# PowerSupp.net
KiCad netlist of a schematic drawn in Altium Designer
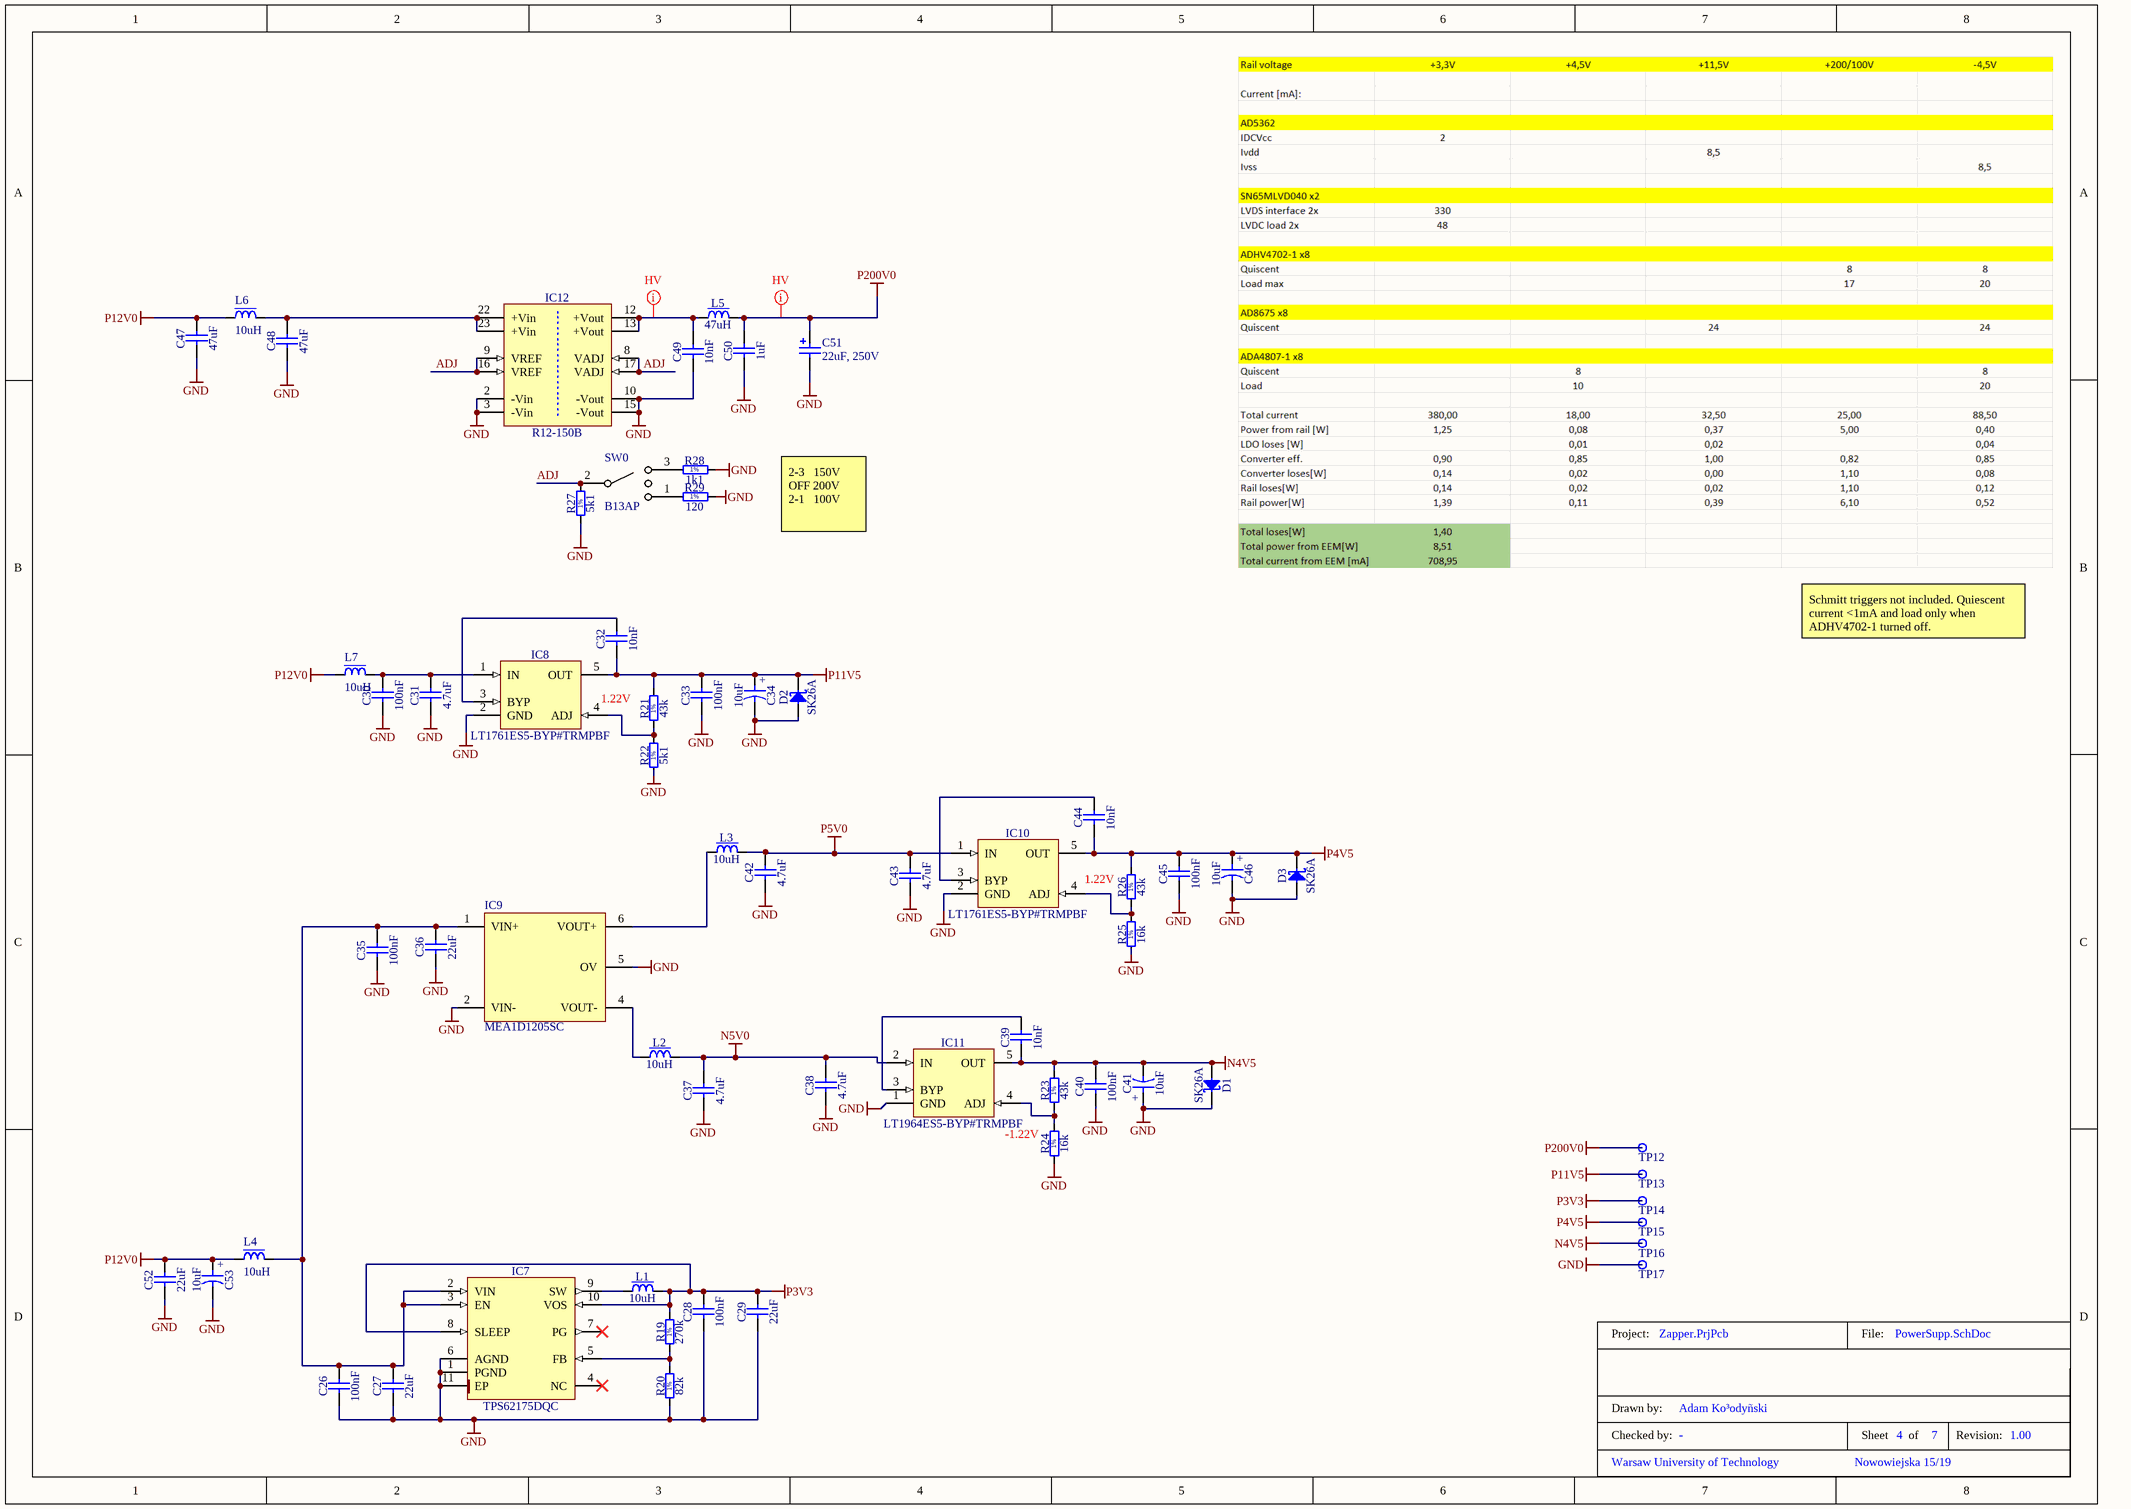
[diagram p0: PowerSupp.SchDoc]

(export (version "E")
  (design (tool "Eeschema 10.0.6"))
  (components
    (comp (ref "C26")
      (value "100nF")
      (footprint "CAPC1005X55N")
      (description "Non-polarised capacitor")
      (fields
        (field (name "PART NUMBER") "CC0402_100NF_16V_10%_X7R")
        (field (name "VOLTAGE") "16V")
        (field (name "AUTHOR") "CERN DEM JLC")
      )
      (libsource (lib "Capacitors") (part "Capacitor - non polarized"))
    )
    (comp (ref "C27")
      (value "22uF")
      (footprint "CAPC2012X135N")
      (description "Non-polarised capacitor")
      (fields
        (field (name "PART NUMBER") "CC0805_22UF_16V_10%_X5R")
        (field (name "VOLTAGE") "16V")
        (field (name "AUTHOR") "CERN DEM JLC")
      )
      (libsource (lib "Capacitors") (part "Capacitor - non polarized"))
    )
    (comp (ref "C28")
      (value "100nF")
      (footprint "CAPC1005X55N")
      (description "Non-polarised capacitor")
      (fields
        (field (name "PART NUMBER") "CC0402_100NF_16V_10%_X7R")
        (field (name "VOLTAGE") "16V")
        (field (name "AUTHOR") "CERN DEM JLC")
      )
      (libsource (lib "Capacitors") (part "Capacitor - non polarized"))
    )
    (comp (ref "C29")
      (value "22uF")
      (footprint "CAPC2012X135N")
      (description "Non-polarised capacitor")
      (fields
        (field (name "PART NUMBER") "CC0805_22UF_16V_10%_X5R")
        (field (name "VOLTAGE") "16V")
        (field (name "AUTHOR") "CERN DEM JLC")
      )
      (libsource (lib "Capacitors") (part "Capacitor - non polarized"))
    )
    (comp (ref "C30")
      (value "100nF")
      (footprint "CAPC1005X55N")
      (description "Non-polarised capacitor")
      (fields
        (field (name "PART NUMBER") "CC0402_100NF_16V_10%_X7R")
        (field (name "VOLTAGE") "16V")
        (field (name "AUTHOR") "CERN DEM JLC")
      )
      (libsource (lib "Capacitors") (part "Capacitor - non polarized"))
    )
    (comp (ref "C31")
      (value "4.7uF")
      (footprint "CAPC2012X135N")
      (description "Non-polarised capacitor")
      (fields
        (field (name "PART NUMBER") "CC0805_4.7UF_16V_10%_X7R")
        (field (name "VOLTAGE") "16V")
        (field (name "AUTHOR") "CERN DEM JLC")
      )
      (libsource (lib "Capacitors") (part "Capacitor - non polarized"))
    )
    (comp (ref "C32")
      (value "10nF")
      (footprint "CAPC1608X87N")
      (description "Non-polarised capacitor")
      (fields
        (field (name "PART NUMBER") "CC0603_10NF_50V_10%_X7R")
        (field (name "VOLTAGE") "50V")
        (field (name "AUTHOR") "CERN DEM JLC")
      )
      (libsource (lib "Capacitors") (part "Capacitor - non polarized"))
    )
    (comp (ref "C33")
      (value "100nF")
      (footprint "CAPC1005X55N")
      (description "Non-polarised capacitor")
      (fields
        (field (name "PART NUMBER") "CC0402_100NF_16V_10%_X7R")
        (field (name "VOLTAGE") "16V")
        (field (name "AUTHOR") "CERN DEM JLC")
      )
      (libsource (lib "Capacitors") (part "Capacitor - non polarized"))
    )
    (comp (ref "C34")
      (value "10uF")
      (footprint "CAPMP3528X210N")
      (description "Polarised capacitor")
      (fields
        (field (name "PART NUMBER") "CTE3528-21_10UF_16V_20%_PANASONIC_TQC")
        (field (name "VOLTAGE") "16V")
        (field (name "AUTHOR") "CERN DEM JLC")
      )
      (libsource (lib "Capacitors") (part "Capacitor - polarized"))
    )
    (comp (ref "C35")
      (value "100nF")
      (footprint "CAPC1005X55N")
      (description "Non-polarised capacitor")
      (fields
        (field (name "PART NUMBER") "CC0402_100NF_16V_10%_X7R")
        (field (name "VOLTAGE") "16V")
        (field (name "AUTHOR") "CERN DEM JLC")
      )
      (libsource (lib "Capacitors") (part "Capacitor - non polarized"))
    )
    (comp (ref "C36")
      (value "22uF")
      (footprint "CAPC2012X135N")
      (description "Non-polarised capacitor")
      (fields
        (field (name "PART NUMBER") "CC0805_22UF_16V_10%_X5R")
        (field (name "VOLTAGE") "16V")
        (field (name "AUTHOR") "CERN DEM JLC")
      )
      (libsource (lib "Capacitors") (part "Capacitor - non polarized"))
    )
    (comp (ref "C37")
      (value "4.7uF")
      (footprint "CAPC2012X135N")
      (description "Non-polarised capacitor")
      (fields
        (field (name "PART NUMBER") "CC0805_4.7UF_16V_10%_X7R")
        (field (name "VOLTAGE") "16V")
        (field (name "AUTHOR") "CERN DEM JLC")
      )
      (libsource (lib "Capacitors") (part "Capacitor - non polarized"))
    )
    (comp (ref "C38")
      (value "4.7uF")
      (footprint "CAPC2012X135N")
      (description "Non-polarised capacitor")
      (fields
        (field (name "PART NUMBER") "CC0805_4.7UF_16V_10%_X7R")
        (field (name "VOLTAGE") "16V")
        (field (name "AUTHOR") "CERN DEM JLC")
      )
      (libsource (lib "Capacitors") (part "Capacitor - non polarized"))
    )
    (comp (ref "C39")
      (value "10nF")
      (footprint "CAPC1608X87N")
      (description "Non-polarised capacitor")
      (fields
        (field (name "PART NUMBER") "CC0603_10NF_50V_10%_X7R")
        (field (name "VOLTAGE") "50V")
        (field (name "AUTHOR") "CERN DEM JLC")
      )
      (libsource (lib "Capacitors") (part "Capacitor - non polarized"))
    )
    (comp (ref "C40")
      (value "100nF")
      (footprint "CAPC1005X55N")
      (description "Non-polarised capacitor")
      (fields
        (field (name "PART NUMBER") "CC0402_100NF_16V_10%_X7R")
        (field (name "VOLTAGE") "16V")
        (field (name "AUTHOR") "CERN DEM JLC")
      )
      (libsource (lib "Capacitors") (part "Capacitor - non polarized"))
    )
    (comp (ref "C41")
      (value "10uF")
      (footprint "CAPMP3528X210N")
      (description "Polarised capacitor")
      (fields
        (field (name "PART NUMBER") "CTE3528-21_10UF_16V_20%_PANASONIC_TQC")
        (field (name "VOLTAGE") "16V")
        (field (name "AUTHOR") "CERN DEM JLC")
      )
      (libsource (lib "Capacitors") (part "Capacitor - polarized"))
    )
    (comp (ref "C42")
      (value "4.7uF")
      (footprint "CAPC2012X135N")
      (description "Non-polarised capacitor")
      (fields
        (field (name "PART NUMBER") "CC0805_4.7UF_16V_10%_X7R")
        (field (name "VOLTAGE") "16V")
        (field (name "AUTHOR") "CERN DEM JLC")
      )
      (libsource (lib "Capacitors") (part "Capacitor - non polarized"))
    )
    (comp (ref "C43")
      (value "4.7uF")
      (footprint "CAPC2012X135N")
      (description "Non-polarised capacitor")
      (fields
        (field (name "PART NUMBER") "CC0805_4.7UF_16V_10%_X7R")
        (field (name "VOLTAGE") "16V")
        (field (name "AUTHOR") "CERN DEM JLC")
      )
      (libsource (lib "Capacitors") (part "Capacitor - non polarized"))
    )
    (comp (ref "C44")
      (value "10nF")
      (footprint "CAPC1608X87N")
      (description "Non-polarised capacitor")
      (fields
        (field (name "PART NUMBER") "CC0603_10NF_50V_10%_X7R")
        (field (name "VOLTAGE") "50V")
        (field (name "AUTHOR") "CERN DEM JLC")
      )
      (libsource (lib "Capacitors") (part "Capacitor - non polarized"))
    )
    (comp (ref "C45")
      (value "100nF")
      (footprint "CAPC1005X55N")
      (description "Non-polarised capacitor")
      (fields
        (field (name "PART NUMBER") "CC0402_100NF_16V_10%_X7R")
        (field (name "VOLTAGE") "16V")
        (field (name "AUTHOR") "CERN DEM JLC")
      )
      (libsource (lib "Capacitors") (part "Capacitor - non polarized"))
    )
    (comp (ref "C46")
      (value "10uF")
      (footprint "CAPMP3528X210N")
      (description "Polarised capacitor")
      (fields
        (field (name "PART NUMBER") "CTE3528-21_10UF_16V_20%_PANASONIC_TQC")
        (field (name "VOLTAGE") "16V")
        (field (name "AUTHOR") "CERN DEM JLC")
      )
      (libsource (lib "Capacitors") (part "Capacitor - polarized"))
    )
    (comp (ref "C47")
      (value "47uF")
      (footprint "CAPC5750X200N")
      (description "Non-polarised capacitor")
      (fields
        (field (name "PART NUMBER") "CC2220_47UF_16V_20%_X7R")
        (field (name "VOLTAGE") "16V")
        (field (name "AUTHOR") "CERN DEM JLC")
      )
      (libsource (lib "Capacitors") (part "Capacitor - non polarized"))
    )
    (comp (ref "C48")
      (value "47uF")
      (footprint "CAPC5750X200N")
      (description "Non-polarised capacitor")
      (fields
        (field (name "PART NUMBER") "CC2220_47UF_16V_20%_X7R")
        (field (name "VOLTAGE") "16V")
        (field (name "AUTHOR") "CERN DEM JLC")
      )
      (libsource (lib "Capacitors") (part "Capacitor - non polarized"))
    )
    (comp (ref "C49")
      (value "10nF")
      (footprint "CAPC3216X88N")
      (description "Non-polarised capacitor")
      (fields
        (field (name "PART NUMBER") "CC1206_10NF_250V_10%_X7R")
        (field (name "VOLTAGE") "250V")
        (field (name "AUTHOR") "CERN DEM MR")
      )
      (libsource (lib "Capacitors") (part "Capacitor - non polarized"))
    )
    (comp (ref "C50")
      (value "1uF")
      (footprint "CAPC5750X270N")
      (description "Non-polarised capacitor")
      (fields
        (field (name "PART NUMBER") "CC2220_1UF_250V_10%_X7T_MURATA_GC355XD72E105KX05L")
        (field (name "VOLTAGE") "250V")
        (field (name "AUTHOR") "CERN DEM JLC")
      )
      (libsource (lib "Capacitors") (part "Capacitor - non polarized"))
    )
    (comp (ref "C51")
      (value "22uF, 250V")
      (footprint "WCAP-AT1H_13x20")
      (description "WCAP-AT1H Aluminum Electrolytic Capacitor, Radial, THT, D13xH20mm, 22uF, 250V")
      (fields
        (field (name "MANUFACTURER PART NUMBER") "860241178002")
        (field (name "MANUFACTURER") "Wurth Elektronik")
      )
      (libsource (lib "CapacitorLibrary") (part "860241178002"))
    )
    (comp (ref "C52")
      (value "22uF")
      (footprint "CAPC2012X135N")
      (description "Non-polarised capacitor")
      (fields
        (field (name "PART NUMBER") "CC0805_22UF_16V_10%_X5R")
        (field (name "VOLTAGE") "16V")
        (field (name "AUTHOR") "CERN DEM JLC")
      )
      (libsource (lib "Capacitors") (part "Capacitor - non polarized"))
    )
    (comp (ref "C53")
      (value "10uF")
      (footprint "CAPMP3528X210N")
      (description "Polarised capacitor")
      (fields
        (field (name "PART NUMBER") "CTE3528-21_10UF_16V_20%_PANASONIC_TQC")
        (field (name "VOLTAGE") "16V")
        (field (name "AUTHOR") "CERN DEM JLC")
      )
      (libsource (lib "Capacitors") (part "Capacitor - polarized"))
    )
    (comp (ref "D1")
      (value "SK26A")
      (footprint "DIOM5126X265N")
      (description "Schottky Diode")
      (fields
        (field (name "VOLTAGE") "60V")
        (field (name "POWER") "2A")
        (field (name "AUTHOR") "CERN DEM JMW")
      )
      (libsource (lib "ICs And Semiconductors") (part "Diode Schottky"))
    )
    (comp (ref "D2")
      (value "SK26A")
      (footprint "DIOM5126X265N")
      (description "Schottky Diode")
      (fields
        (field (name "VOLTAGE") "60V")
        (field (name "POWER") "2A")
        (field (name "AUTHOR") "CERN DEM JMW")
      )
      (libsource (lib "ICs And Semiconductors") (part "Diode Schottky"))
    )
    (comp (ref "D3")
      (value "SK26A")
      (footprint "DIOM5126X265N")
      (description "Schottky Diode")
      (fields
        (field (name "VOLTAGE") "60V")
        (field (name "POWER") "2A")
        (field (name "AUTHOR") "CERN DEM JMW")
      )
      (libsource (lib "ICs And Semiconductors") (part "Diode Schottky"))
    )
    (comp (ref "IC7")
      (value "TPS62175DQC")
      (footprint "SON50P200X300X80-11N-R94X250")
      (description "4.75-28VDC to 1-6VDC, 500mA Step-Down Converter With Sleep Mode")
      (fields (field (name "MANUFACTURER") "TEXAS INSTRUMENTS") (field (name "AUTHOR") "CERN DEM JMW"))
      (libsource (lib "ICs And Semiconductors") (part "TPS62175"))
    )
    (comp (ref "IC8")
      (value "LT1761ES5-BYP#TRMPBF")
      (footprint "SOT95P280X100-5N")
      (description "100mA, Low Noise, LDO Micropower Adjustable Regulator in SOT-23")
      (fields (field (name "MANUFACTURER") "LINEAR TECHNOLOGY") (field (name "AUTHOR") "CERN DEM MR"))
      (libsource (lib "ICs And Semiconductors") (part "LT1761-BYP"))
    )
    (comp (ref "IC9")
      (value "MEA1D1205SC")
      (footprint "MURA-SIP-5_V")
      (description "Module DC-DC 2-OUT 5V/-5V 0.1A/-0.1A 1W 5-Pin SIP Tube")
      (libsource (lib "InzLib") (part "MEA1D1205SC"))
    )
    (comp (ref "IC10")
      (value "LT1761ES5-BYP#TRMPBF")
      (footprint "SOT95P280X100-5N")
      (description "100mA, Low Noise, LDO Micropower Adjustable Regulator in SOT-23")
      (fields (field (name "MANUFACTURER") "LINEAR TECHNOLOGY") (field (name "AUTHOR") "CERN DEM MR"))
      (libsource (lib "ICs And Semiconductors") (part "LT1761-BYP"))
    )
    (comp (ref "IC11")
      (value "LT1964ES5-BYP#TRMPBF")
      (footprint "SOT95P280X100-5N")
      (description "200mA, Low Noise, Low Dropout Negative Micropower Regulator")
      (fields (field (name "MANUFACTURER") "LINEAR TECHNOLOGY") (field (name "AUTHOR") "CERN DEM MR"))
      (libsource (lib "ICs And Semiconductors") (part "LT1964-BYP"))
    )
    (comp (ref "IC12")
      (value "R12-150B")
      (footprint "DCDC_RECOM_Rxx-B")
      (description "RECOM, Rxx-B Series, Single Output DCDC Converter")
      (fields (field (name "MANUFACTURER") "RECOM") (field (name "AUTHOR") "CERN DEM MR"))
      (libsource (lib "ICs And Semiconductors") (part "DCDC_RECOM_Rxx-B_Single Output"))
    )
    (comp (ref "L1")
      (value "10uH")
      (footprint "IND_MURATA-PS_8400")
      (description "Inductor With Core")
      (fields
        (field (name "PART NUMBER") "IND_10UH_10%_MURATA-PS_8400")
        (field (name "POWER") "950mA")
        (field (name "AUTHOR") "CERN DEM JLC")
      )
      (libsource (lib "Inductors & Transformers") (part "Inductor With Magnetic core"))
    )
    (comp (ref "L2")
      (value "10uH")
      (footprint "IND_MURATA-PS_8400")
      (description "Inductor With Core")
      (fields
        (field (name "PART NUMBER") "IND_10UH_10%_MURATA-PS_8400")
        (field (name "POWER") "950mA")
        (field (name "AUTHOR") "CERN DEM JLC")
      )
      (libsource (lib "Inductors & Transformers") (part "Inductor With Magnetic core"))
    )
    (comp (ref "L3")
      (value "10uH")
      (footprint "IND_MURATA-PS_8400")
      (description "Inductor With Core")
      (fields
        (field (name "PART NUMBER") "IND_10UH_10%_MURATA-PS_8400")
        (field (name "POWER") "950mA")
        (field (name "AUTHOR") "CERN DEM JLC")
      )
      (libsource (lib "Inductors & Transformers") (part "Inductor With Magnetic core"))
    )
    (comp (ref "L4")
      (value "10uH")
      (footprint "IND_MURATA-PS_8400")
      (description "Inductor With Core")
      (fields
        (field (name "PART NUMBER") "IND_10UH_10%_MURATA-PS_8400")
        (field (name "POWER") "950mA")
        (field (name "AUTHOR") "CERN DEM JLC")
      )
      (libsource (lib "Inductors & Transformers") (part "Inductor With Magnetic core"))
    )
    (comp (ref "L5")
      (value "47uH")
      (footprint "IND_MURATA-PS_8400")
      (description "Inductor With Core")
      (fields
        (field (name "PART NUMBER") "IND_47UH_10%_MURATA-PS_8400")
        (field (name "POWER") "420mA")
        (field (name "AUTHOR") "CERN DEM JLC")
      )
      (libsource (lib "Inductors & Transformers") (part "Inductor With Magnetic core"))
    )
    (comp (ref "L6")
      (value "10uH")
      (footprint "IND_MURATA-PS_8400")
      (description "Inductor With Core")
      (fields
        (field (name "PART NUMBER") "IND_10UH_10%_MURATA-PS_8400")
        (field (name "POWER") "950mA")
        (field (name "AUTHOR") "CERN DEM JLC")
      )
      (libsource (lib "Inductors & Transformers") (part "Inductor With Magnetic core"))
    )
    (comp (ref "L7")
      (value "10uH")
      (footprint "IND_MURATA-PS_8400")
      (description "Inductor With Core")
      (fields
        (field (name "PART NUMBER") "IND_10UH_10%_MURATA-PS_8400")
        (field (name "POWER") "950mA")
        (field (name "AUTHOR") "CERN DEM JLC")
      )
      (libsource (lib "Inductors & Transformers") (part "Inductor With Magnetic core"))
    )
    (comp (ref "R19")
      (value "270k")
      (footprint "RESC1608X55N")
      (description "Resistor - 1%")
      (fields
        (field (name "PART NUMBER") "R0603_270K_1%_0.1W_100PPM")
        (field (name "POWER") "0.1W")
        (field (name "AUTHOR") "CERN DEM JLC")
      )
      (libsource (lib "Resistors") (part "Resistor - 1%"))
    )
    (comp (ref "R20")
      (value "82k")
      (footprint "RESC1608X55N")
      (description "Resistor - 1%")
      (fields
        (field (name "PART NUMBER") "R0603_82K_1%_0.1W_100PPM")
        (field (name "POWER") "0.1W")
        (field (name "AUTHOR") "CERN DEM JLC")
      )
      (libsource (lib "Resistors") (part "Resistor - 1%"))
    )
    (comp (ref "R21")
      (value "43k")
      (footprint "RESC1608X55N")
      (description "Resistor - 1%")
      (fields
        (field (name "PART NUMBER") "R0603_43K_1%_0.1W_100PPM")
        (field (name "POWER") "0.1W")
        (field (name "AUTHOR") "CERN DEM JLC")
      )
      (libsource (lib "Resistors") (part "Resistor - 1%"))
    )
    (comp (ref "R22")
      (value "5k1")
      (footprint "RESC1608X55N")
      (description "Resistor - 1%")
      (fields
        (field (name "PART NUMBER") "R0603_5K1_1%_0.1W_100PPM")
        (field (name "POWER") "0.1W")
        (field (name "AUTHOR") "CERN DEM JLC")
      )
      (libsource (lib "Resistors") (part "Resistor - 1%"))
    )
    (comp (ref "R23")
      (value "43k")
      (footprint "RESC1608X55N")
      (description "Resistor - 1%")
      (fields
        (field (name "PART NUMBER") "R0603_43K_1%_0.1W_100PPM")
        (field (name "POWER") "0.1W")
        (field (name "AUTHOR") "CERN DEM JLC")
      )
      (libsource (lib "Resistors") (part "Resistor - 1%"))
    )
    (comp (ref "R24")
      (value "16k")
      (footprint "RESC1608X55N")
      (description "Resistor - 1%")
      (fields
        (field (name "PART NUMBER") "R0603_16K_1%_0.1W_100PPM")
        (field (name "POWER") "0.1W")
        (field (name "AUTHOR") "CERN DEM JLC")
      )
      (libsource (lib "Resistors") (part "Resistor - 1%"))
    )
    (comp (ref "R25")
      (value "16k")
      (footprint "RESC1608X55N")
      (description "Resistor - 1%")
      (fields
        (field (name "PART NUMBER") "R0603_16K_1%_0.1W_100PPM")
        (field (name "POWER") "0.1W")
        (field (name "AUTHOR") "CERN DEM JLC")
      )
      (libsource (lib "Resistors") (part "Resistor - 1%"))
    )
    (comp (ref "R26")
      (value "43k")
      (footprint "RESC1608X55N")
      (description "Resistor - 1%")
      (fields
        (field (name "PART NUMBER") "R0603_43K_1%_0.1W_100PPM")
        (field (name "POWER") "0.1W")
        (field (name "AUTHOR") "CERN DEM JLC")
      )
      (libsource (lib "Resistors") (part "Resistor - 1%"))
    )
    (comp (ref "R27")
      (value "5k1")
      (footprint "RESC1608X55N")
      (description "Resistor - 1%")
      (fields
        (field (name "PART NUMBER") "R0603_5K1_1%_0.1W_100PPM")
        (field (name "POWER") "0.1W")
        (field (name "AUTHOR") "CERN DEM JLC")
      )
      (libsource (lib "Resistors") (part "Resistor - 1%"))
    )
    (comp (ref "R28")
      (value "1k1")
      (footprint "RESC1608X55N")
      (description "Resistor - 1%")
      (fields
        (field (name "PART NUMBER") "R0603_1K1_1%_0.1W_100PPM")
        (field (name "POWER") "0.1W")
        (field (name "AUTHOR") "CERN DEM JLC")
      )
      (libsource (lib "Resistors") (part "Resistor - 1%"))
    )
    (comp (ref "R29")
      (value "120")
      (footprint "RESC1608X55N")
      (description "Resistor - 1%")
      (fields
        (field (name "PART NUMBER") "R0603_120R_1%_0.1W_100PPM")
        (field (name "POWER") "0.1W")
        (field (name "AUTHOR") "CERN DEM JLC")
      )
      (libsource (lib "Resistors") (part "Resistor - 1%"))
    )
    (comp (ref "SW0")
      (value "B13AP")
      (footprint "B13AP")
      (description "Switch;  Sealed;  Anti-Static Toggle;  SPDT;  ON-OFF-ON;  Str PC;  No Cap;  0.4A;  28VAC/DC")
      (libsource (lib "InzLib") (part "B13AP"))
    )
    (comp (ref "TitleBlock4") (value "TitleBlock") (libsource (lib "InzLib") (part "TitleBlock")))
    (comp (ref "TP12")
      (value "Test Point")
      (footprint "TPS127")
      (fields (field (name "PART NUMBER") "SMD_PAD_1.27X1.27MM") (field (name "AUTHOR") "CERN DEM JLC"))
      (libsource (lib "Eletro-mechanical") (part "Test Point"))
    )
    (comp (ref "TP13")
      (value "Test Point")
      (footprint "TPS127")
      (fields (field (name "PART NUMBER") "SMD_PAD_1.27X1.27MM") (field (name "AUTHOR") "CERN DEM JLC"))
      (libsource (lib "Eletro-mechanical") (part "Test Point"))
    )
    (comp (ref "TP14")
      (value "Test Point")
      (footprint "TPS127")
      (fields (field (name "PART NUMBER") "SMD_PAD_1.27X1.27MM") (field (name "AUTHOR") "CERN DEM JLC"))
      (libsource (lib "Eletro-mechanical") (part "Test Point"))
    )
    (comp (ref "TP15")
      (value "Test Point")
      (footprint "TPS127")
      (fields (field (name "PART NUMBER") "SMD_PAD_1.27X1.27MM") (field (name "AUTHOR") "CERN DEM JLC"))
      (libsource (lib "Eletro-mechanical") (part "Test Point"))
    )
    (comp (ref "TP16")
      (value "Test Point")
      (footprint "TPS127")
      (fields (field (name "PART NUMBER") "SMD_PAD_1.27X1.27MM") (field (name "AUTHOR") "CERN DEM JLC"))
      (libsource (lib "Eletro-mechanical") (part "Test Point"))
    )
    (comp (ref "TP17")
      (value "Test Point")
      (footprint "TPS127")
      (fields (field (name "PART NUMBER") "SMD_PAD_1.27X1.27MM") (field (name "AUTHOR") "CERN DEM JLC"))
      (libsource (lib "Eletro-mechanical") (part "Test Point"))
    )
  )
  (nets
    (net (code "1") (name "/ADJ") (class "Default")
      (node (ref "IC12") (pin "16") (pinfunction "VREF_16") (pintype "input"))
      (node (ref "IC12") (pin "17") (pinfunction "VADJ_17") (pintype "input"))
      (node (ref "IC12") (pin "8") (pinfunction "VADJ_8") (pintype "input"))
      (node (ref "IC12") (pin "9") (pinfunction "VREF_9") (pintype "input"))
      (node (ref "R27") (pin "2") (pinfunction "2_2") (pintype "passive"))
      (node (ref "SW0") (pin "2") (pinfunction "C_2") (pintype "passive"))
    )
    (net (code "2") (name "GND") (class "Default")
      (node (ref "C26") (pin "1") (pinfunction "1_1") (pintype "passive"))
      (node (ref "C27") (pin "1") (pinfunction "1_1") (pintype "passive"))
      (node (ref "C28") (pin "1") (pinfunction "1_1") (pintype "passive"))
      (node (ref "C29") (pin "1") (pinfunction "1_1") (pintype "passive"))
      (node (ref "C30") (pin "1") (pinfunction "1_1") (pintype "passive"))
      (node (ref "C31") (pin "1") (pinfunction "1_1") (pintype "passive"))
      (node (ref "C33") (pin "1") (pinfunction "1_1") (pintype "passive"))
      (node (ref "C34") (pin "2") (pinfunction "2_2") (pintype "passive"))
      (node (ref "C35") (pin "1") (pinfunction "1_1") (pintype "passive"))
      (node (ref "C36") (pin "1") (pinfunction "1_1") (pintype "passive"))
      (node (ref "C37") (pin "1") (pinfunction "1_1") (pintype "passive"))
      (node (ref "C38") (pin "1") (pinfunction "1_1") (pintype "passive"))
      (node (ref "C40") (pin "1") (pinfunction "1_1") (pintype "passive"))
      (node (ref "C41") (pin "1") (pinfunction "1_1") (pintype "passive"))
      (node (ref "C42") (pin "1") (pinfunction "1_1") (pintype "passive"))
      (node (ref "C43") (pin "1") (pinfunction "1_1") (pintype "passive"))
      (node (ref "C45") (pin "1") (pinfunction "1_1") (pintype "passive"))
      (node (ref "C46") (pin "2") (pinfunction "2_2") (pintype "passive"))
      (node (ref "C47") (pin "1") (pinfunction "1_1") (pintype "passive"))
      (node (ref "C48") (pin "1") (pinfunction "1_1") (pintype "passive"))
      (node (ref "C49") (pin "1") (pinfunction "1_1") (pintype "passive"))
      (node (ref "C50") (pin "1") (pinfunction "1_1") (pintype "passive"))
      (node (ref "C51") (pin "1") (pinfunction "N_1") (pintype "passive"))
      (node (ref "C52") (pin "1") (pinfunction "1_1") (pintype "passive"))
      (node (ref "C53") (pin "2") (pinfunction "2_2") (pintype "passive"))
      (node (ref "D1") (pin "1") (pinfunction "C_1") (pintype "passive"))
      (node (ref "D2") (pin "2") (pinfunction "A_2") (pintype "passive"))
      (node (ref "D3") (pin "2") (pinfunction "A_2") (pintype "passive"))
      (node (ref "IC10") (pin "2") (pinfunction "GND_2") (pintype "power_in"))
      (node (ref "IC11") (pin "1") (pinfunction "GND_1") (pintype "power_in"))
      (node (ref "IC12") (pin "10") (pinfunction "-Vout_10") (pintype "power_in"))
      (node (ref "IC12") (pin "15") (pinfunction "-Vout_15") (pintype "power_in"))
      (node (ref "IC12") (pin "2") (pinfunction "-Vin_2") (pintype "power_in"))
      (node (ref "IC12") (pin "3") (pinfunction "-Vin_3") (pintype "power_in"))
      (node (ref "IC7") (pin "1") (pinfunction "PGND_1") (pintype "power_in"))
      (node (ref "IC7") (pin "11") (pinfunction "EP_11") (pintype "power_in"))
      (node (ref "IC7") (pin "6") (pinfunction "AGND_6") (pintype "power_in"))
      (node (ref "IC8") (pin "2") (pinfunction "GND_2") (pintype "power_in"))
      (node (ref "IC9") (pin "2") (pinfunction "VIN-_2") (pintype "power_in"))
      (node (ref "IC9") (pin "5") (pinfunction "OV_5") (pintype "power_in"))
      (node (ref "R20") (pin "1") (pinfunction "1_1") (pintype "passive"))
      (node (ref "R22") (pin "1") (pinfunction "1_1") (pintype "passive"))
      (node (ref "R24") (pin "1") (pinfunction "1_1") (pintype "passive"))
      (node (ref "R25") (pin "1") (pinfunction "1_1") (pintype "passive"))
      (node (ref "R27") (pin "1") (pinfunction "1_1") (pintype "passive"))
      (node (ref "R28") (pin "2") (pinfunction "2_2") (pintype "passive"))
      (node (ref "R29") (pin "2") (pinfunction "2_2") (pintype "passive"))
      (node (ref "TP17") (pin "1") (pinfunction "1_1") (pintype "bidirectional"))
    )
    (net (code "3") (name "N4V5") (class "Default")
      (node (ref "C39") (pin "1") (pinfunction "1_1") (pintype "passive"))
      (node (ref "C40") (pin "2") (pinfunction "2_2") (pintype "passive"))
      (node (ref "C41") (pin "2") (pinfunction "2_2") (pintype "passive"))
      (node (ref "D1") (pin "2") (pinfunction "A_2") (pintype "passive"))
      (node (ref "IC11") (pin "5") (pinfunction "OUT_5") (pintype "power_in"))
      (node (ref "R23") (pin "2") (pinfunction "2_2") (pintype "passive"))
      (node (ref "TP16") (pin "1") (pinfunction "1_1") (pintype "bidirectional"))
    )
    (net (code "4") (name "N5V0") (class "Default")
      (node (ref "C37") (pin "2") (pinfunction "2_2") (pintype "passive"))
      (node (ref "C38") (pin "2") (pinfunction "2_2") (pintype "passive"))
      (node (ref "IC11") (pin "2") (pinfunction "IN_2") (pintype "input"))
      (node (ref "L2") (pin "2") (pinfunction "2_2") (pintype "passive"))
    )
    (net (code "5") (name "Net-(C48-Pad2)") (class "Default")
      (node (ref "C48") (pin "2") (pinfunction "2_2") (pintype "passive"))
      (node (ref "IC12") (pin "22") (pinfunction "+Vin_22") (pintype "power_in"))
      (node (ref "IC12") (pin "23") (pinfunction "+Vin_23") (pintype "power_in"))
      (node (ref "L6") (pin "2") (pinfunction "2_2") (pintype "passive"))
    )
    (net (code "6") (name "Net-(C49-Pad2)") (class "Default")
      (node (ref "C49") (pin "2") (pinfunction "2_2") (pintype "passive"))
      (node (ref "IC12") (pin "12") (pinfunction "+Vout_12") (pintype "power_in"))
      (node (ref "IC12") (pin "13") (pinfunction "+Vout_13") (pintype "power_in"))
      (node (ref "L5") (pin "1") (pinfunction "1_1") (pintype "passive"))
    )
    (net (code "7") (name "Net-(IC7-EN)") (class "Default")
      (node (ref "C26") (pin "2") (pinfunction "2_2") (pintype "passive"))
      (node (ref "C27") (pin "2") (pinfunction "2_2") (pintype "passive"))
      (node (ref "C35") (pin "2") (pinfunction "2_2") (pintype "passive"))
      (node (ref "C36") (pin "2") (pinfunction "2_2") (pintype "passive"))
      (node (ref "IC7") (pin "2") (pinfunction "VIN_2") (pintype "input"))
      (node (ref "IC7") (pin "3") (pinfunction "EN_3") (pintype "input"))
      (node (ref "IC9") (pin "1") (pinfunction "VIN+_1") (pintype "power_in"))
      (node (ref "L4") (pin "2") (pinfunction "2_2") (pintype "passive"))
    )
    (net (code "8") (name "Net-(IC7-FB)") (class "Default")
      (node (ref "IC7") (pin "5") (pinfunction "FB_5") (pintype "input"))
      (node (ref "R19") (pin "1") (pinfunction "1_1") (pintype "passive"))
      (node (ref "R20") (pin "2") (pinfunction "2_2") (pintype "passive"))
    )
    (net (code "9") (name "Net-(IC7-SW)") (class "Default")
      (node (ref "IC7") (pin "9") (pinfunction "SW_9") (pintype "output"))
      (node (ref "L1") (pin "1") (pinfunction "1_1") (pintype "passive"))
    )
    (net (code "10") (name "Net-(IC8-ADJ)") (class "Default")
      (node (ref "IC8") (pin "4") (pinfunction "ADJ_4") (pintype "input"))
      (node (ref "R21") (pin "1") (pinfunction "1_1") (pintype "passive"))
      (node (ref "R22") (pin "2") (pinfunction "2_2") (pintype "passive"))
    )
    (net (code "11") (name "Net-(IC8-BYP)") (class "Default")
      (node (ref "C32") (pin "2") (pinfunction "2_2") (pintype "passive"))
      (node (ref "IC8") (pin "3") (pinfunction "BYP_3") (pintype "input"))
    )
    (net (code "12") (name "Net-(IC8-IN)") (class "Default")
      (node (ref "C30") (pin "2") (pinfunction "2_2") (pintype "passive"))
      (node (ref "C31") (pin "2") (pinfunction "2_2") (pintype "passive"))
      (node (ref "IC8") (pin "1") (pinfunction "IN_1") (pintype "input"))
      (node (ref "L7") (pin "2") (pinfunction "2_2") (pintype "passive"))
    )
    (net (code "13") (name "Net-(IC9-VOUT+)") (class "Default")
      (node (ref "IC9") (pin "6") (pinfunction "VOUT+_6") (pintype "power_in"))
      (node (ref "L3") (pin "1") (pinfunction "1_1") (pintype "passive"))
    )
    (net (code "14") (name "Net-(IC9-VOUT-)") (class "Default")
      (node (ref "IC9") (pin "4") (pinfunction "VOUT-_4") (pintype "power_in"))
      (node (ref "L2") (pin "1") (pinfunction "1_1") (pintype "passive"))
    )
    (net (code "15") (name "Net-(IC10-ADJ)") (class "Default")
      (node (ref "IC10") (pin "4") (pinfunction "ADJ_4") (pintype "input"))
      (node (ref "R25") (pin "2") (pinfunction "2_2") (pintype "passive"))
      (node (ref "R26") (pin "1") (pinfunction "1_1") (pintype "passive"))
    )
    (net (code "16") (name "Net-(IC10-BYP)") (class "Default")
      (node (ref "C44") (pin "2") (pinfunction "2_2") (pintype "passive"))
      (node (ref "IC10") (pin "3") (pinfunction "BYP_3") (pintype "input"))
    )
    (net (code "17") (name "Net-(IC11-ADJ)") (class "Default")
      (node (ref "IC11") (pin "4") (pinfunction "ADJ_4") (pintype "input"))
      (node (ref "R23") (pin "1") (pinfunction "1_1") (pintype "passive"))
      (node (ref "R24") (pin "2") (pinfunction "2_2") (pintype "passive"))
    )
    (net (code "18") (name "Net-(IC11-BYP)") (class "Default")
      (node (ref "C39") (pin "2") (pinfunction "2_2") (pintype "passive"))
      (node (ref "IC11") (pin "3") (pinfunction "BYP_3") (pintype "input"))
    )
    (net (code "19") (name "Net-(SW0-NC)") (class "Default")
      (node (ref "R28") (pin "1") (pinfunction "1_1") (pintype "passive"))
      (node (ref "SW0") (pin "3") (pinfunction "NC_3") (pintype "passive"))
    )
    (net (code "20") (name "Net-(SW0-NO)") (class "Default")
      (node (ref "R29") (pin "1") (pinfunction "1_1") (pintype "passive"))
      (node (ref "SW0") (pin "1") (pinfunction "NO_1") (pintype "passive"))
    )
    (net (code "21") (name "P3V3") (class "Default")
      (node (ref "C28") (pin "2") (pinfunction "2_2") (pintype "passive"))
      (node (ref "C29") (pin "2") (pinfunction "2_2") (pintype "passive"))
      (node (ref "IC7") (pin "10") (pinfunction "VOS_10") (pintype "input"))
      (node (ref "IC7") (pin "8") (pinfunction "SLEEP_8") (pintype "input"))
      (node (ref "L1") (pin "2") (pinfunction "2_2") (pintype "passive"))
      (node (ref "R19") (pin "2") (pinfunction "2_2") (pintype "passive"))
      (node (ref "TP14") (pin "1") (pinfunction "1_1") (pintype "bidirectional"))
    )
    (net (code "22") (name "P4V5") (class "Default")
      (node (ref "C44") (pin "1") (pinfunction "1_1") (pintype "passive"))
      (node (ref "C45") (pin "2") (pinfunction "2_2") (pintype "passive"))
      (node (ref "C46") (pin "1") (pinfunction "1_1") (pintype "passive"))
      (node (ref "D3") (pin "1") (pinfunction "C_1") (pintype "passive"))
      (node (ref "IC10") (pin "5") (pinfunction "OUT_5") (pintype "power_in"))
      (node (ref "R26") (pin "2") (pinfunction "2_2") (pintype "passive"))
      (node (ref "TP15") (pin "1") (pinfunction "1_1") (pintype "bidirectional"))
    )
    (net (code "23") (name "P5V0") (class "Default")
      (node (ref "C42") (pin "2") (pinfunction "2_2") (pintype "passive"))
      (node (ref "C43") (pin "2") (pinfunction "2_2") (pintype "passive"))
      (node (ref "IC10") (pin "1") (pinfunction "IN_1") (pintype "input"))
      (node (ref "L3") (pin "2") (pinfunction "2_2") (pintype "passive"))
    )
    (net (code "24") (name "P11V5") (class "Default")
      (node (ref "C32") (pin "1") (pinfunction "1_1") (pintype "passive"))
      (node (ref "C33") (pin "2") (pinfunction "2_2") (pintype "passive"))
      (node (ref "C34") (pin "1") (pinfunction "1_1") (pintype "passive"))
      (node (ref "D2") (pin "1") (pinfunction "C_1") (pintype "passive"))
      (node (ref "IC8") (pin "5") (pinfunction "OUT_5") (pintype "power_in"))
      (node (ref "R21") (pin "2") (pinfunction "2_2") (pintype "passive"))
      (node (ref "TP13") (pin "1") (pinfunction "1_1") (pintype "bidirectional"))
    )
    (net (code "25") (name "P12V0") (class "Default")
      (node (ref "C47") (pin "2") (pinfunction "2_2") (pintype "passive"))
      (node (ref "C52") (pin "2") (pinfunction "2_2") (pintype "passive"))
      (node (ref "C53") (pin "1") (pinfunction "1_1") (pintype "passive"))
      (node (ref "L4") (pin "1") (pinfunction "1_1") (pintype "passive"))
      (node (ref "L6") (pin "1") (pinfunction "1_1") (pintype "passive"))
      (node (ref "L7") (pin "1") (pinfunction "1_1") (pintype "passive"))
    )
    (net (code "26") (name "P200V0") (class "Default")
      (node (ref "C50") (pin "2") (pinfunction "2_2") (pintype "passive"))
      (node (ref "C51") (pin "2") (pinfunction "P_2") (pintype "passive"))
      (node (ref "L5") (pin "2") (pinfunction "2_2") (pintype "passive"))
      (node (ref "TP12") (pin "1") (pinfunction "1_1") (pintype "bidirectional"))
    )
    (net (code "27") (name "unconnected-(IC7-NC-Pad4)") (class "Default")
      (node (ref "IC7") (pin "4") (pinfunction "NC_4") (pintype "passive+no_connect"))
    )
    (net (code "28") (name "unconnected-(IC7-PG-Pad7)") (class "Default")
      (node (ref "IC7") (pin "7") (pinfunction "PG_7") (pintype "output+no_connect"))
    )
  )
)
